# Analog_Signal.net
KiCad netlist of a schematic drawn in Altium Designer
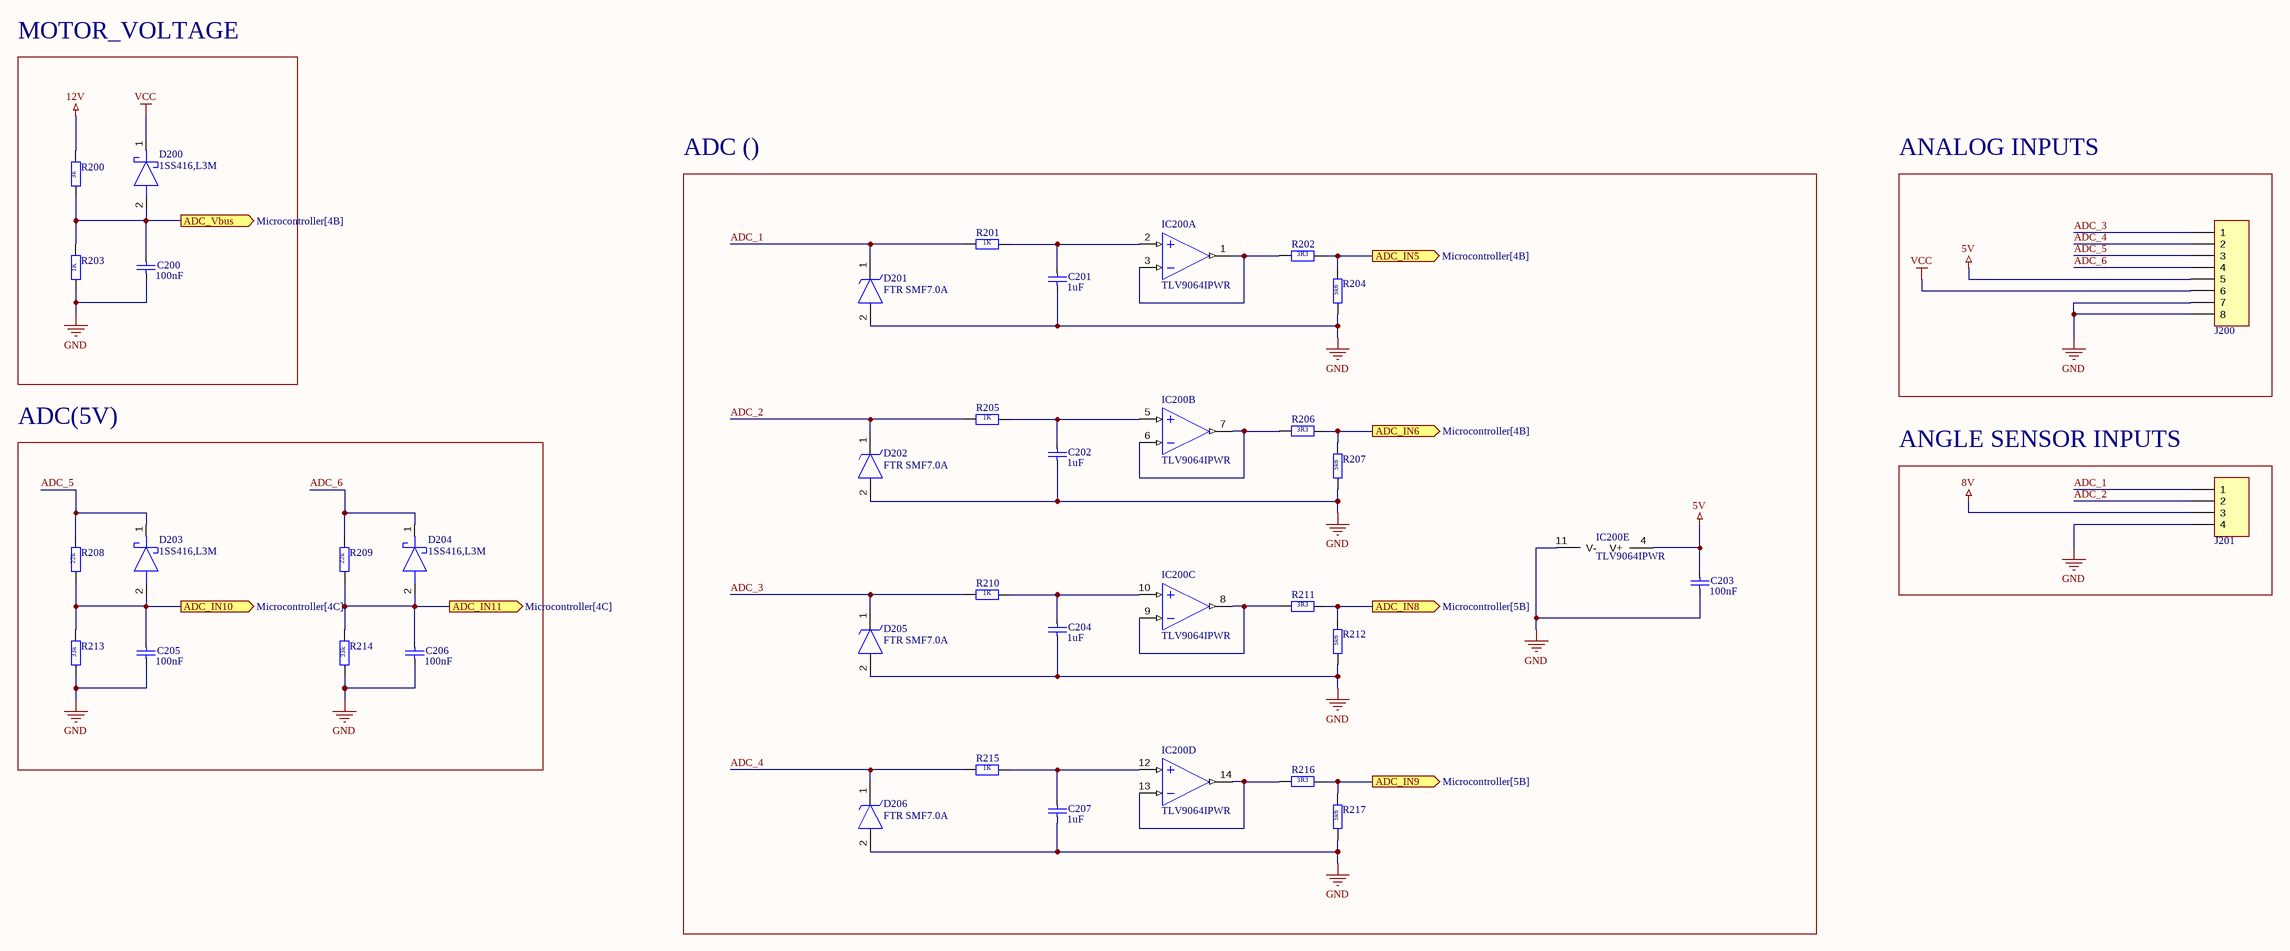
[diagram p0: Analog_Signal.SchDoc]

(export (version "E")
  (design (tool "Eeschema 10.0.6"))
  (components
    (comp (ref "C200")
      (value "100nF")
      (footprint "CAPC1608X09N")
      (fields (field (name "MPN") "06033C104KAT4A") (field (name "Comment") "C"))
      (libsource (lib "My_lib") (part "C"))
    )
    (comp (ref "C201")
      (value "1uF")
      (footprint "CAPC1608X09N")
      (fields (field (name "MPN") "CL10B105KP8NNNC") (field (name "Comment") "C"))
      (libsource (lib "My_lib") (part "C"))
    )
    (comp (ref "C202")
      (value "1uF")
      (footprint "CAPC1608X09N")
      (fields (field (name "MPN") "CL10B105KP8NNNC") (field (name "Comment") "C"))
      (libsource (lib "My_lib") (part "C"))
    )
    (comp (ref "C203")
      (value "100nF")
      (footprint "CAPC1608X09N")
      (fields (field (name "MPN") "06033C104KAT4A") (field (name "Comment") "C"))
      (libsource (lib "My_lib") (part "C"))
    )
    (comp (ref "C204")
      (value "1uF")
      (footprint "CAPC1608X09N")
      (fields (field (name "MPN") "CL10B105KP8NNNC") (field (name "Comment") "C"))
      (libsource (lib "My_lib") (part "C"))
    )
    (comp (ref "C205")
      (value "100nF")
      (footprint "CAPC1608X09N")
      (fields (field (name "MPN") "06033C104KAT4A") (field (name "Comment") "C"))
      (libsource (lib "My_lib") (part "C"))
    )
    (comp (ref "C206")
      (value "100nF")
      (footprint "CAPC1608X09N")
      (fields (field (name "MPN") "06033C104KAT4A") (field (name "Comment") "C"))
      (libsource (lib "My_lib") (part "C"))
    )
    (comp (ref "C207")
      (value "1uF")
      (footprint "CAPC1608X09N")
      (fields (field (name "MPN") "CL10B105KP8NNNC") (field (name "Comment") "C"))
      (libsource (lib "My_lib") (part "C"))
    )
    (comp (ref "D200")
      (value "1SS416,L3M")
      (footprint "SamacSys:SODFL1006X45N")
      (description "Schottky Diode")
      (fields (field (name "MPN") "1SS416,L3M(B") (field (name "LCSC PART NUMBER") "C2943683"))
      (libsource (lib "*") (part "1SS416,L3M"))
    )
    (comp (ref "D201")
      (value "FTR SMF7.0A")
      (footprint "SamacSys:SMF70ATP")
      (description "TVS Diode (Uni-directional)")
      (fields (field (name "MPN") "SMF7.0A") (field (name "LCSC PART NUMBER") "C707468"))
      (libsource (lib "*") (part "SMF7.0A-TP"))
    )
    (comp (ref "D202")
      (value "FTR SMF7.0A")
      (footprint "SamacSys:SMF70ATP")
      (description "TVS Diode (Uni-directional)")
      (fields (field (name "MPN") "SMF7.0A") (field (name "LCSC PART NUMBER") "C707468"))
      (libsource (lib "*") (part "SMF7.0A-TP"))
    )
    (comp (ref "D203")
      (value "1SS416,L3M")
      (footprint "SamacSys:SODFL1006X45N")
      (description "Schottky Diode")
      (fields (field (name "MPN") "1SS416,L3M(B") (field (name "LCSC PART NUMBER") "C2943683"))
      (libsource (lib "*") (part "1SS416,L3M"))
    )
    (comp (ref "D204")
      (value "1SS416,L3M")
      (footprint "SamacSys:SODFL1006X45N")
      (description "Schottky Diode")
      (fields (field (name "MPN") "1SS416,L3M(B") (field (name "LCSC PART NUMBER") "C2943683"))
      (libsource (lib "*") (part "1SS416,L3M"))
    )
    (comp (ref "D205")
      (value "FTR SMF7.0A")
      (footprint "SamacSys:SMF70ATP")
      (description "TVS Diode (Uni-directional)")
      (fields (field (name "MPN") "SMF7.0A") (field (name "LCSC PART NUMBER") "C707468"))
      (libsource (lib "*") (part "SMF7.0A-TP"))
    )
    (comp (ref "D206")
      (value "FTR SMF7.0A")
      (footprint "SamacSys:SMF70ATP")
      (description "TVS Diode (Uni-directional)")
      (fields (field (name "MPN") "SMF7.0A") (field (name "LCSC PART NUMBER") "C707468"))
      (libsource (lib "*") (part "SMF7.0A-TP"))
    )
    (comp (ref "IC200")
      (value "TLV9064IPWR")
      (footprint "SamacSys:SOP65P640X120-14N")
      (description "Integrated Circuit")
      (fields
        (field (name "MOUSER PART NUMBER") "595-TLV9064IPWR")
        (field (name "LCSC PART NUMBER") "C779410")
      )
      (libsource (lib "SamacSys") (part "TLV9064IPWR"))
    )
    (comp (ref "J200")
      (value "XH2.54-8P")
      (footprint "XH2.54-8P")
      (fields (field (name "MPN") "XY-XH2.54-8A11"))
      (libsource (lib "My_lib") (part "XH2.54-8P"))
    )
    (comp (ref "J201")
      (value "XH2.54-4P")
      (footprint "XH2.54-4P")
      (fields (field (name "MPN") "BX-XH2.54-4PZZ"))
      (libsource (lib "My_lib") (part "XH2.54-4P"))
    )
    (comp (ref "R200")
      (value "3k")
      (footprint "RESC1608X06N")
      (fields (field (name "MPN") "0603WAF3001T5E") (field (name "Comment") "R"))
      (libsource (lib "My_lib") (part "R"))
    )
    (comp (ref "R201")
      (value "1K")
      (footprint "RESC1608X06N")
      (fields (field (name "MPN") "0603WAF1001T5E") (field (name "Comment") "R"))
      (libsource (lib "") (part "R_1"))
    )
    (comp (ref "R202")
      (value "3R3")
      (footprint "RESC1608X06N")
      (fields (field (name "MPN") "0603WAF3301T5E") (field (name "Comment") "R"))
      (libsource (lib "") (part "R_2"))
    )
    (comp (ref "R203")
      (value "1K")
      (footprint "RESC1608X06N")
      (fields (field (name "MPN") "0603WAF1001T5E") (field (name "Comment") "R"))
      (libsource (lib "My_lib") (part "R"))
    )
    (comp (ref "R204")
      (value "5k6")
      (footprint "RESC1608X06N")
      (fields (field (name "MPN") "0603WAF5601T5E") (field (name "Comment") "R"))
      (libsource (lib "My_lib") (part "R"))
    )
    (comp (ref "R205")
      (value "1K")
      (footprint "RESC1608X06N")
      (fields (field (name "MPN") "0603WAF1001T5E") (field (name "Comment") "R"))
      (libsource (lib "") (part "R_1"))
    )
    (comp (ref "R206")
      (value "3R3")
      (footprint "RESC1608X06N")
      (fields (field (name "MPN") "0603WAF3301T5E") (field (name "Comment") "R"))
      (libsource (lib "") (part "R_2"))
    )
    (comp (ref "R207")
      (value "5k6")
      (footprint "RESC1608X06N")
      (fields (field (name "MPN") "0603WAF5601T5E") (field (name "Comment") "R"))
      (libsource (lib "My_lib") (part "R"))
    )
    (comp (ref "R208")
      (value "22k")
      (footprint "RESC1608X06N")
      (fields (field (name "MPN") "0603WAF2202T5E") (field (name "Comment") "R"))
      (libsource (lib "My_lib") (part "R"))
    )
    (comp (ref "R209")
      (value "22k")
      (footprint "RESC1608X06N")
      (fields (field (name "MPN") "0603WAF2202T5E") (field (name "Comment") "R"))
      (libsource (lib "My_lib") (part "R"))
    )
    (comp (ref "R210")
      (value "1K")
      (footprint "RESC1608X06N")
      (fields (field (name "MPN") "0603WAF1001T5E") (field (name "Comment") "R"))
      (libsource (lib "") (part "R_1"))
    )
    (comp (ref "R211")
      (value "3R3")
      (footprint "RESC1608X06N")
      (fields (field (name "MPN") "0603WAF3301T5E") (field (name "Comment") "R"))
      (libsource (lib "") (part "R_2"))
    )
    (comp (ref "R212")
      (value "5k6")
      (footprint "RESC1608X06N")
      (fields (field (name "MPN") "0603WAF5601T5E") (field (name "Comment") "R"))
      (libsource (lib "My_lib") (part "R"))
    )
    (comp (ref "R213")
      (value "33k")
      (footprint "RESC1608X06N")
      (fields (field (name "MPN") "RC0603FR-0733KL") (field (name "Comment") "R"))
      (libsource (lib "My_lib") (part "R"))
    )
    (comp (ref "R214")
      (value "33k")
      (footprint "RESC1608X06N")
      (fields (field (name "MPN") "RC0603FR-0733KL") (field (name "Comment") "R"))
      (libsource (lib "My_lib") (part "R"))
    )
    (comp (ref "R215")
      (value "1K")
      (footprint "RESC1608X06N")
      (fields (field (name "MPN") "0603WAF1001T5E") (field (name "Comment") "R"))
      (libsource (lib "") (part "R_1"))
    )
    (comp (ref "R216")
      (value "3R3")
      (footprint "RESC1608X06N")
      (fields (field (name "MPN") "0603WAF3301T5E") (field (name "Comment") "R"))
      (libsource (lib "") (part "R_2"))
    )
    (comp (ref "R217")
      (value "5k6")
      (footprint "RESC1608X06N")
      (fields (field (name "MPN") "0603WAF5601T5E") (field (name "Comment") "R"))
      (libsource (lib "My_lib") (part "R"))
    )
  )
  (nets
    (net (code "1") (name "/ADC_1") (class "Default")
      (node (ref "D201") (pin "1") (pinfunction "K_1") (pintype "passive"))
      (node (ref "J201") (pin "1") (pinfunction "1_1") (pintype "passive"))
      (node (ref "R201") (pin "2") (pinfunction "2_2") (pintype "passive"))
    )
    (net (code "2") (name "/ADC_2") (class "Default")
      (node (ref "D202") (pin "1") (pinfunction "K_1") (pintype "passive"))
      (node (ref "J201") (pin "2") (pinfunction "2_2") (pintype "passive"))
      (node (ref "R205") (pin "2") (pinfunction "2_2") (pintype "passive"))
    )
    (net (code "3") (name "/ADC_3") (class "Default")
      (node (ref "D205") (pin "1") (pinfunction "K_1") (pintype "passive"))
      (node (ref "J200") (pin "1") (pinfunction "1_1") (pintype "passive"))
      (node (ref "R210") (pin "2") (pinfunction "2_2") (pintype "passive"))
    )
    (net (code "4") (name "/ADC_4") (class "Default")
      (node (ref "D206") (pin "1") (pinfunction "K_1") (pintype "passive"))
      (node (ref "J200") (pin "2") (pinfunction "2_2") (pintype "passive"))
      (node (ref "R215") (pin "2") (pinfunction "2_2") (pintype "passive"))
    )
    (net (code "5") (name "/ADC_5") (class "Default")
      (node (ref "D203") (pin "1") (pinfunction "K_1") (pintype "passive"))
      (node (ref "J200") (pin "3") (pinfunction "3_3") (pintype "passive"))
      (node (ref "R208") (pin "2") (pinfunction "2_2") (pintype "passive"))
    )
    (net (code "6") (name "/ADC_6") (class "Default")
      (node (ref "D204") (pin "1") (pinfunction "K_1") (pintype "passive"))
      (node (ref "J200") (pin "4") (pinfunction "4_4") (pintype "passive"))
      (node (ref "R209") (pin "2") (pinfunction "2_2") (pintype "passive"))
    )
    (net (code "7") (name "/ADC_IN5") (class "Default")
      (node (ref "R202") (pin "1") (pinfunction "1_1") (pintype "passive"))
      (node (ref "R204") (pin "2") (pinfunction "2_2") (pintype "passive"))
    )
    (net (code "8") (name "/ADC_IN6") (class "Default")
      (node (ref "R206") (pin "1") (pinfunction "1_1") (pintype "passive"))
      (node (ref "R207") (pin "2") (pinfunction "2_2") (pintype "passive"))
    )
    (net (code "9") (name "/ADC_IN8") (class "Default")
      (node (ref "R211") (pin "1") (pinfunction "1_1") (pintype "passive"))
      (node (ref "R212") (pin "2") (pinfunction "2_2") (pintype "passive"))
    )
    (net (code "10") (name "/ADC_IN9") (class "Default")
      (node (ref "R216") (pin "1") (pinfunction "1_1") (pintype "passive"))
      (node (ref "R217") (pin "2") (pinfunction "2_2") (pintype "passive"))
    )
    (net (code "11") (name "/ADC_IN10") (class "Default")
      (node (ref "C205") (pin "2") (pinfunction "2_2") (pintype "passive"))
      (node (ref "D203") (pin "2") (pinfunction "A_2") (pintype "passive"))
      (node (ref "R208") (pin "1") (pinfunction "1_1") (pintype "passive"))
      (node (ref "R213") (pin "2") (pinfunction "2_2") (pintype "passive"))
    )
    (net (code "12") (name "/ADC_IN11") (class "Default")
      (node (ref "C206") (pin "2") (pinfunction "2_2") (pintype "passive"))
      (node (ref "D204") (pin "2") (pinfunction "A_2") (pintype "passive"))
      (node (ref "R209") (pin "1") (pinfunction "1_1") (pintype "passive"))
      (node (ref "R214") (pin "2") (pinfunction "2_2") (pintype "passive"))
    )
    (net (code "13") (name "/ADC_Vbus") (class "Default")
      (node (ref "C200") (pin "2") (pinfunction "2_2") (pintype "passive"))
      (node (ref "D200") (pin "2") (pinfunction "A_2") (pintype "passive"))
      (node (ref "R200") (pin "1") (pinfunction "1_1") (pintype "passive"))
      (node (ref "R203") (pin "2") (pinfunction "2_2") (pintype "passive"))
    )
    (net (code "14") (name "5V") (class "Default")
      (node (ref "C203") (pin "2") (pinfunction "2_2") (pintype "passive"))
      (node (ref "IC200") (pin "4") (pinfunction "V+_4") (pintype "power_in"))
      (node (ref "J200") (pin "5") (pinfunction "5_5") (pintype "passive"))
    )
    (net (code "15") (name "8V") (class "Default")
      (node (ref "J201") (pin "3") (pinfunction "3_3") (pintype "passive"))
    )
    (net (code "16") (name "12V") (class "Default")
      (node (ref "R200") (pin "2") (pinfunction "2_2") (pintype "passive"))
    )
    (net (code "17") (name "GND") (class "Default")
      (node (ref "C200") (pin "1") (pinfunction "1_1") (pintype "passive"))
      (node (ref "C201") (pin "1") (pinfunction "1_1") (pintype "passive"))
      (node (ref "C202") (pin "1") (pinfunction "1_1") (pintype "passive"))
      (node (ref "C203") (pin "1") (pinfunction "1_1") (pintype "passive"))
      (node (ref "C204") (pin "1") (pinfunction "1_1") (pintype "passive"))
      (node (ref "C205") (pin "1") (pinfunction "1_1") (pintype "passive"))
      (node (ref "C206") (pin "1") (pinfunction "1_1") (pintype "passive"))
      (node (ref "C207") (pin "1") (pinfunction "1_1") (pintype "passive"))
      (node (ref "D201") (pin "2") (pinfunction "A_2") (pintype "passive"))
      (node (ref "D202") (pin "2") (pinfunction "A_2") (pintype "passive"))
      (node (ref "D205") (pin "2") (pinfunction "A_2") (pintype "passive"))
      (node (ref "D206") (pin "2") (pinfunction "A_2") (pintype "passive"))
      (node (ref "IC200") (pin "11") (pinfunction "V-_11") (pintype "power_in"))
      (node (ref "J200") (pin "7") (pinfunction "7_7") (pintype "passive"))
      (node (ref "J200") (pin "8") (pinfunction "8_8") (pintype "passive"))
      (node (ref "J201") (pin "4") (pinfunction "4_4") (pintype "passive"))
      (node (ref "R203") (pin "1") (pinfunction "1_1") (pintype "passive"))
      (node (ref "R204") (pin "1") (pinfunction "1_1") (pintype "passive"))
      (node (ref "R207") (pin "1") (pinfunction "1_1") (pintype "passive"))
      (node (ref "R212") (pin "1") (pinfunction "1_1") (pintype "passive"))
      (node (ref "R213") (pin "1") (pinfunction "1_1") (pintype "passive"))
      (node (ref "R214") (pin "1") (pinfunction "1_1") (pintype "passive"))
      (node (ref "R217") (pin "1") (pinfunction "1_1") (pintype "passive"))
    )
    (net (code "18") (name "Net-(IC200A-IN1+)") (class "Default")
      (node (ref "IC200") (pin "1") (pinfunction "OUT1_1") (pintype "output"))
      (node (ref "IC200") (pin "3") (pinfunction "IN1+_3") (pintype "input"))
      (node (ref "R202") (pin "2") (pinfunction "2_2") (pintype "passive"))
    )
    (net (code "19") (name "Net-(IC200A-IN1-)") (class "Default")
      (node (ref "C201") (pin "2") (pinfunction "2_2") (pintype "passive"))
      (node (ref "IC200") (pin "2") (pinfunction "IN1-_2") (pintype "input"))
      (node (ref "R201") (pin "1") (pinfunction "1_1") (pintype "passive"))
    )
    (net (code "20") (name "Net-(IC200B-IN2+)") (class "Default")
      (node (ref "C202") (pin "2") (pinfunction "2_2") (pintype "passive"))
      (node (ref "IC200") (pin "5") (pinfunction "IN2+_5") (pintype "input"))
      (node (ref "R205") (pin "1") (pinfunction "1_1") (pintype "passive"))
    )
    (net (code "21") (name "Net-(IC200B-IN2-)") (class "Default")
      (node (ref "IC200") (pin "6") (pinfunction "IN2-_6") (pintype "input"))
      (node (ref "IC200") (pin "7") (pinfunction "OUT2_7") (pintype "output"))
      (node (ref "R206") (pin "2") (pinfunction "2_2") (pintype "passive"))
    )
    (net (code "22") (name "Net-(IC200C-IN3+)") (class "Default")
      (node (ref "C204") (pin "2") (pinfunction "2_2") (pintype "passive"))
      (node (ref "IC200") (pin "10") (pinfunction "IN3+_10") (pintype "input"))
      (node (ref "R210") (pin "1") (pinfunction "1_1") (pintype "passive"))
    )
    (net (code "23") (name "Net-(IC200C-IN3-)") (class "Default")
      (node (ref "IC200") (pin "8") (pinfunction "OUT3_8") (pintype "output"))
      (node (ref "IC200") (pin "9") (pinfunction "IN3-_9") (pintype "input"))
      (node (ref "R211") (pin "2") (pinfunction "2_2") (pintype "passive"))
    )
    (net (code "24") (name "Net-(IC200D-IN4+)") (class "Default")
      (node (ref "C207") (pin "2") (pinfunction "2_2") (pintype "passive"))
      (node (ref "IC200") (pin "12") (pinfunction "IN4+_12") (pintype "input"))
      (node (ref "R215") (pin "1") (pinfunction "1_1") (pintype "passive"))
    )
    (net (code "25") (name "Net-(IC200D-IN4-)") (class "Default")
      (node (ref "IC200") (pin "13") (pinfunction "IN4-_13") (pintype "input"))
      (node (ref "IC200") (pin "14") (pinfunction "OUT4_14") (pintype "output"))
      (node (ref "R216") (pin "2") (pinfunction "2_2") (pintype "passive"))
    )
    (net (code "26") (name "VCC") (class "Default")
      (node (ref "D200") (pin "1") (pinfunction "K_1") (pintype "passive"))
      (node (ref "J200") (pin "6") (pinfunction "6_6") (pintype "passive"))
    )
  )
)
